# BB-PCF.net
KiCad netlist of a schematic drawn in EAGLE
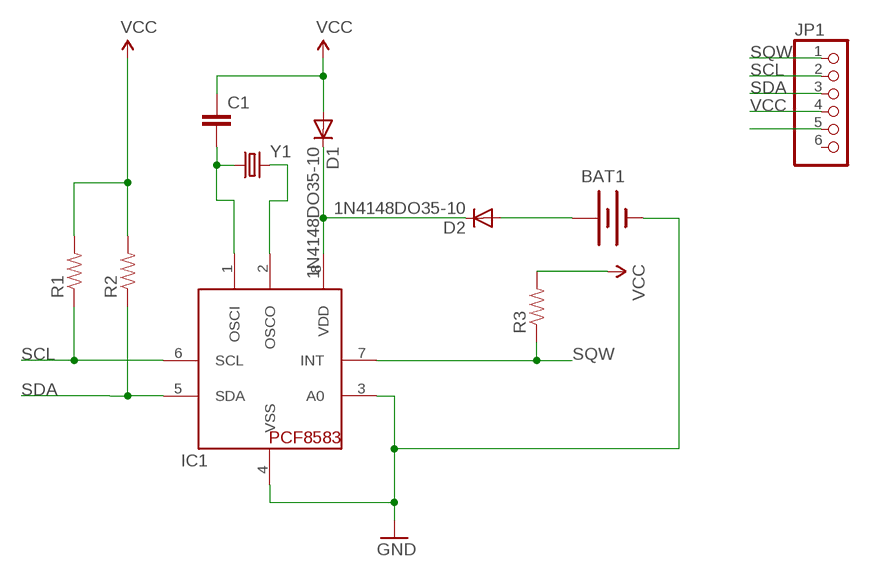
[diagram p0: schematic, sheet 1]

(export (version "E")
  (design (tool "Eeschema 10.0.6"))
  (components
    (comp (ref "BAT1")
      (value "BATTERY20PTH")
      (footprint "eagle-import:BATTCOM_20MM_PTH")
      (libsource (lib "eagle-import") (part "BATTERY20PTH"))
    )
    (comp (ref "C1")
      (value "CAPPTH")
      (footprint "eagle-import:CAP-PTH-SMALL")
      (libsource (lib "eagle-import") (part "CAPPTH"))
    )
    (comp (ref "D1")
      (value "1N4148DO35-10")
      (footprint "eagle-import:DO35-10")
      (libsource (lib "eagle-import") (part "1N4148DO35-10"))
    )
    (comp (ref "D2")
      (value "1N4148DO35-10")
      (footprint "eagle-import:DO35-10")
      (libsource (lib "eagle-import") (part "1N4148DO35-10"))
    )
    (comp (ref "IC1")
      (value "PCF8583")
      (footprint "eagle-import:DIL08")
      (libsource (lib "eagle-import") (part "PCF8583"))
    )
    (comp (ref "JP1")
      (value "PINHD-1X6")
      (footprint "eagle-import:1X06")
      (libsource (lib "eagle-import") (part "PINHD-1X6"))
    )
    (comp (ref "R1")
      (value "RESISTORPTH-1/4W")
      (footprint "eagle-import:AXIAL-0.4")
      (libsource (lib "eagle-import") (part "RESISTORPTH-1/4W"))
    )
    (comp (ref "R2")
      (value "RESISTORPTH-1/4W")
      (footprint "eagle-import:AXIAL-0.4")
      (libsource (lib "eagle-import") (part "RESISTORPTH-1/4W"))
    )
    (comp (ref "R3")
      (value "RESISTORPTH-1/4W")
      (footprint "eagle-import:AXIAL-0.4")
      (libsource (lib "eagle-import") (part "RESISTORPTH-1/4W"))
    )
    (comp (ref "Y1")
      (value "CRYSTALTC26H_EZ")
      (footprint "eagle-import:TC26HEZ")
      (libsource (lib "eagle-import") (part "CRYSTALTC26H_EZ"))
    )
  )
  (nets
    (net (code "1") (name "/SCL") (class "Default")
      (node (ref "IC1") (pin "6") (pinfunction "SCL_6") (pintype "bidirectional"))
      (node (ref "JP1") (pin "2") (pinfunction "2_2") (pintype "passive"))
      (node (ref "R1") (pin "P$1") (pinfunction "1_P$1") (pintype "passive"))
    )
    (net (code "2") (name "/SDA") (class "Default")
      (node (ref "IC1") (pin "5") (pinfunction "SDA_5") (pintype "bidirectional"))
      (node (ref "JP1") (pin "3") (pinfunction "3_3") (pintype "passive"))
      (node (ref "R2") (pin "P$1") (pinfunction "1_P$1") (pintype "passive"))
    )
    (net (code "3") (name "/SQW") (class "Default")
      (node (ref "IC1") (pin "7") (pinfunction "INT_7") (pintype "bidirectional"))
      (node (ref "JP1") (pin "1") (pinfunction "1_1") (pintype "passive"))
      (node (ref "R3") (pin "P$1") (pinfunction "1_P$1") (pintype "passive"))
    )
    (net (code "4") (name "GND") (class "Default")
      (node (ref "BAT1") (pin "2") (pinfunction "-_2") (pintype "power_in"))
      (node (ref "IC1") (pin "3") (pinfunction "A0_3") (pintype "power_in"))
      (node (ref "IC1") (pin "4") (pinfunction "VSS_4") (pintype "power_in"))
      (node (ref "JP1") (pin "5") (pinfunction "5_5") (pintype "passive"))
    )
    (net (code "5") (name "Net-(BAT1-+)") (class "Default")
      (node (ref "BAT1") (pin "1") (pinfunction "+_1") (pintype "power_in"))
      (node (ref "D2") (pin "A") (pinfunction "A_A") (pintype "passive"))
    )
    (net (code "6") (name "Net-(IC1-OSCI)") (class "Default")
      (node (ref "C1") (pin "2") (pinfunction "2_2") (pintype "passive"))
      (node (ref "IC1") (pin "1") (pinfunction "OSCI_1") (pintype "passive"))
      (node (ref "Y1") (pin "1") (pinfunction "1_1") (pintype "passive"))
    )
    (net (code "7") (name "Net-(IC1-OSCO)") (class "Default")
      (node (ref "IC1") (pin "2") (pinfunction "OSCO_2") (pintype "passive"))
      (node (ref "Y1") (pin "2") (pinfunction "2_2") (pintype "passive"))
    )
    (net (code "8") (name "Net-(IC1-VDD)") (class "Default")
      (node (ref "D1") (pin "C") (pinfunction "C_C") (pintype "passive"))
      (node (ref "D2") (pin "C") (pinfunction "C_C") (pintype "passive"))
      (node (ref "IC1") (pin "8") (pinfunction "VDD_8") (pintype "power_in"))
    )
    (net (code "9") (name "VCC") (class "Default")
      (node (ref "C1") (pin "1") (pinfunction "1_1") (pintype "passive"))
      (node (ref "D1") (pin "A") (pinfunction "A_A") (pintype "passive"))
      (node (ref "JP1") (pin "4") (pinfunction "4_4") (pintype "passive"))
      (node (ref "R1") (pin "P$2") (pinfunction "2_P$2") (pintype "passive"))
      (node (ref "R2") (pin "P$2") (pinfunction "2_P$2") (pintype "passive"))
      (node (ref "R3") (pin "P$2") (pinfunction "2_P$2") (pintype "passive"))
    )
    (net (code "10") (name "unconnected-(JP1-Pad6)") (class "Default")
      (node (ref "JP1") (pin "6") (pinfunction "6_6") (pintype "passive"))
    )
  )
)
